# MCU.net
KiCad netlist of a schematic drawn in Altium Designer
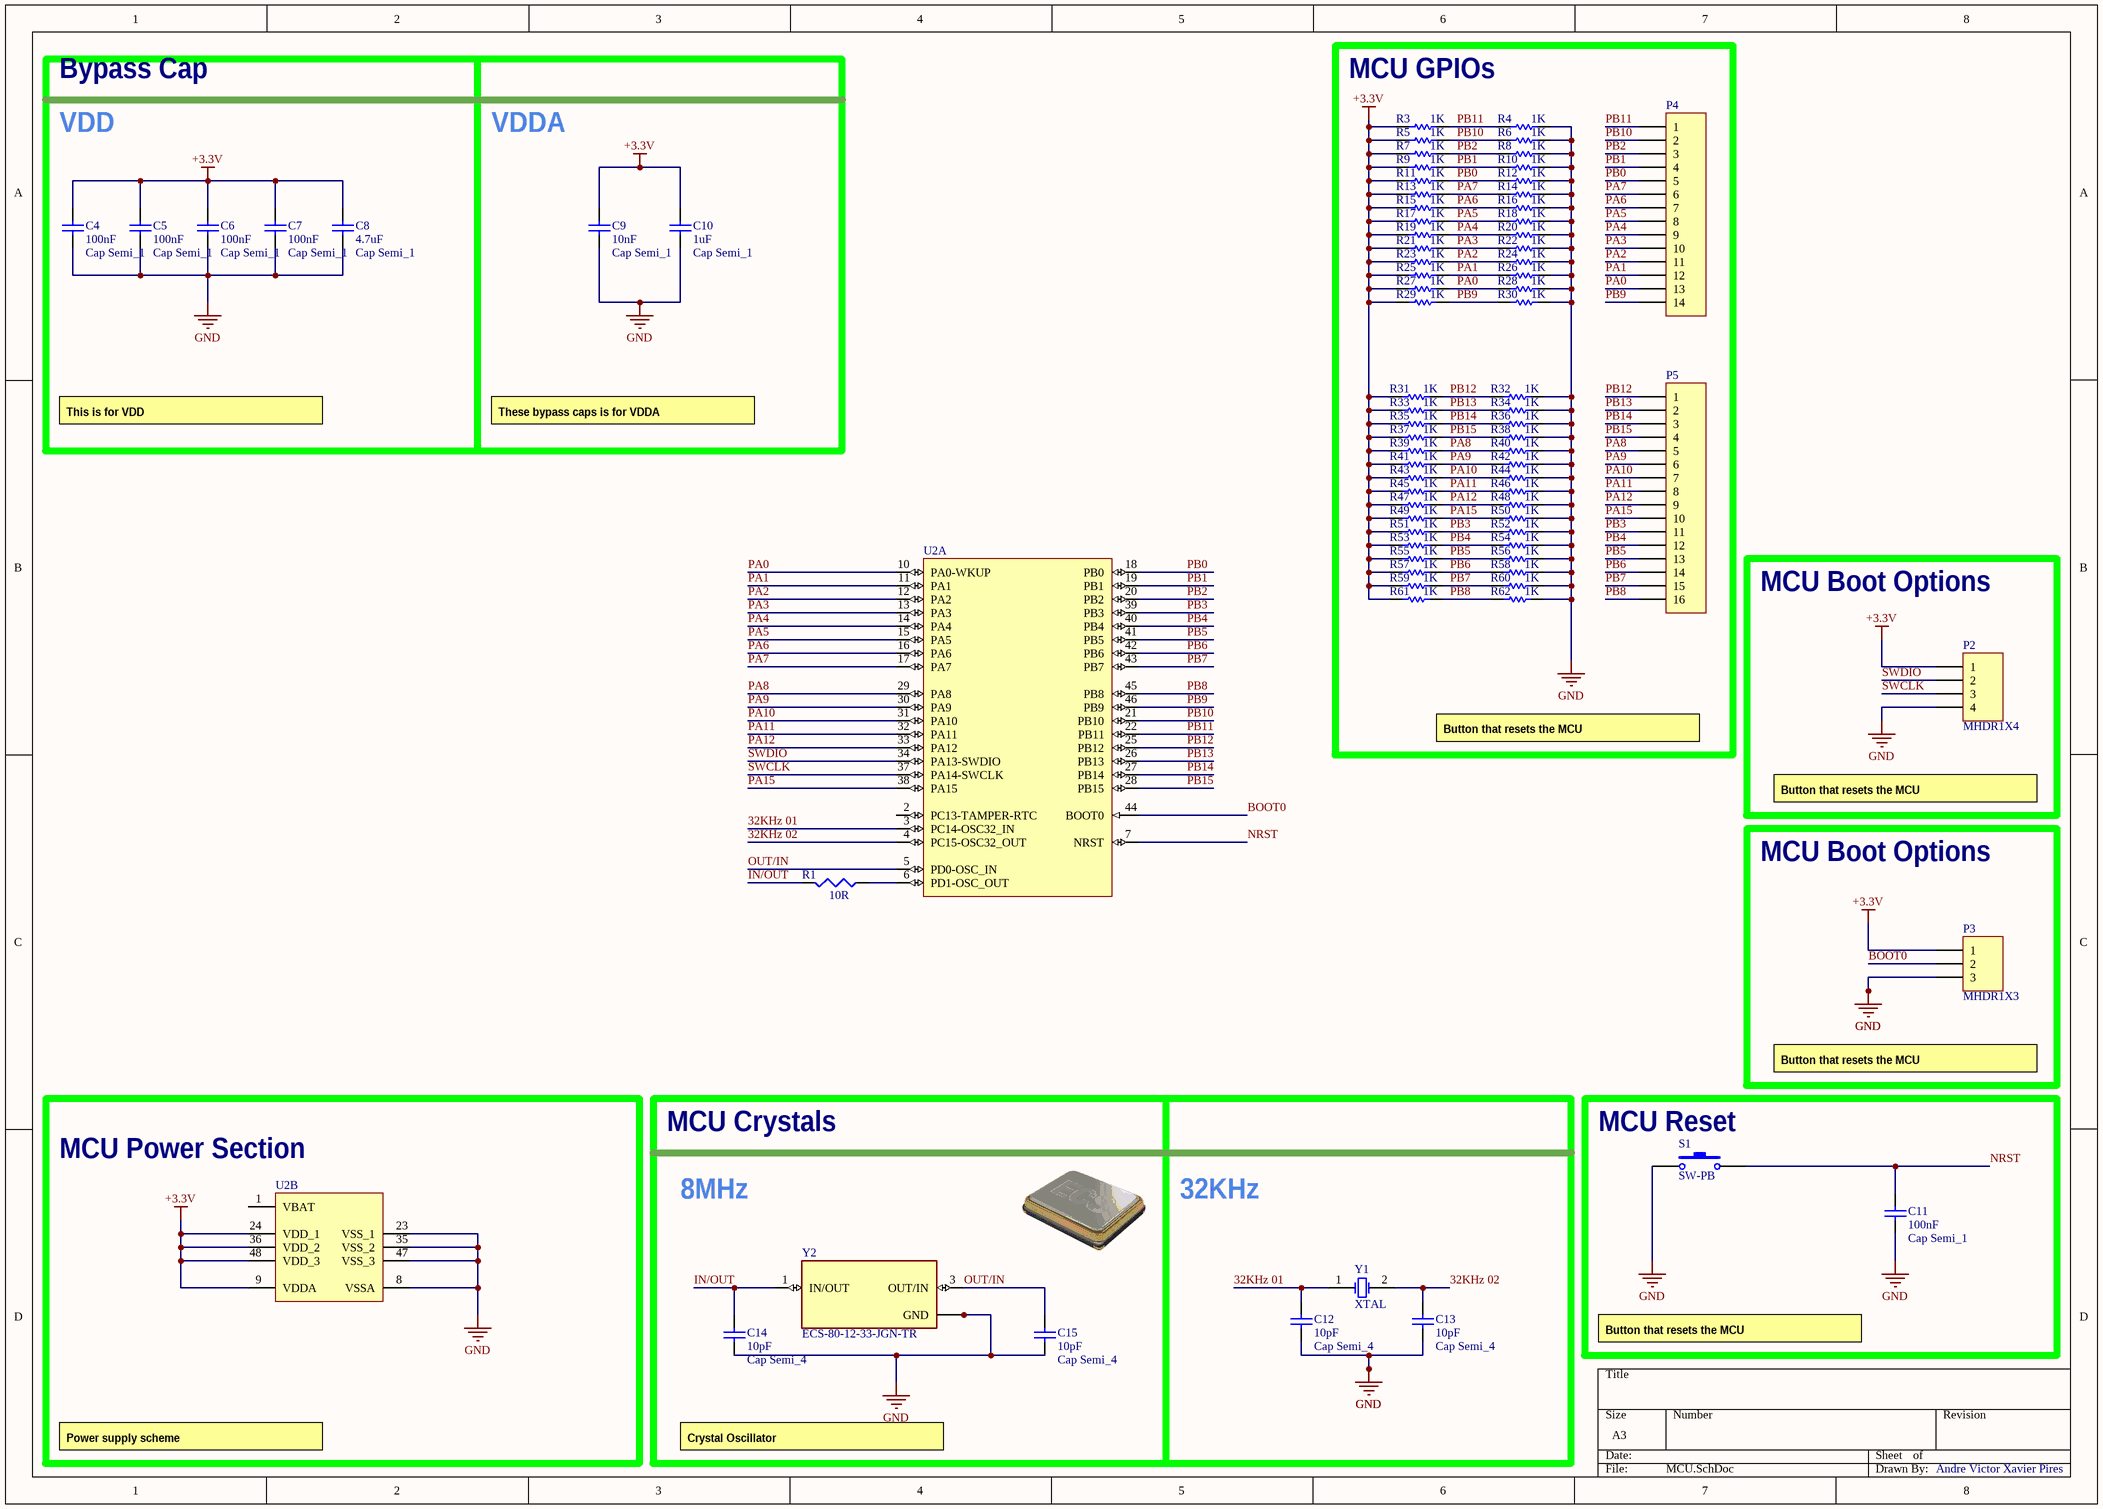
[diagram p0: MCU.SchDoc]

(export (version "E")
  (design (tool "Eeschema 10.0.6"))
  (components
    (comp (ref "C4")
      (value "Cap Semi_1")
      (footprint "1608[0603]cap")
      (description "Capacitor (Semiconductor SIM Model)")
      (fields (field (name "ALTIUM_VALUE") "100nF") (field (name "PUBLISHER") "Altium Limited"))
      (libsource (lib "smartmcu") (part "Cap Semi_1"))
    )
    (comp (ref "C5")
      (value "Cap Semi_1")
      (footprint "1608[0603]cap")
      (description "Capacitor (Semiconductor SIM Model)")
      (fields (field (name "ALTIUM_VALUE") "100nF") (field (name "PUBLISHER") "Altium Limited"))
      (libsource (lib "smartmcu") (part "Cap Semi_1"))
    )
    (comp (ref "C6")
      (value "Cap Semi_1")
      (footprint "1608[0603]cap")
      (description "Capacitor (Semiconductor SIM Model)")
      (fields (field (name "ALTIUM_VALUE") "100nF") (field (name "PUBLISHER") "Altium Limited"))
      (libsource (lib "smartmcu") (part "Cap Semi_1"))
    )
    (comp (ref "C7")
      (value "Cap Semi_1")
      (footprint "1608[0603]cap")
      (description "Capacitor (Semiconductor SIM Model)")
      (fields (field (name "ALTIUM_VALUE") "100nF") (field (name "PUBLISHER") "Altium Limited"))
      (libsource (lib "smartmcu") (part "Cap Semi_1"))
    )
    (comp (ref "C8")
      (value "Cap Semi_1")
      (footprint "1608[0603]cap")
      (description "Capacitor (Semiconductor SIM Model)")
      (fields (field (name "ALTIUM_VALUE") "4.7uF") (field (name "PUBLISHER") "Altium Limited"))
      (libsource (lib "smartmcu") (part "Cap Semi_1_1"))
    )
    (comp (ref "C9")
      (value "Cap Semi_1")
      (footprint "1608[0603]cap")
      (description "Capacitor (Semiconductor SIM Model)")
      (fields (field (name "ALTIUM_VALUE") "10nF") (field (name "PUBLISHER") "Altium Limited"))
      (libsource (lib "smartmcu") (part "Cap Semi_1_2"))
    )
    (comp (ref "C10")
      (value "Cap Semi_1")
      (footprint "1608[0603]cap")
      (description "Capacitor (Semiconductor SIM Model)")
      (fields (field (name "ALTIUM_VALUE") "1uF") (field (name "PUBLISHER") "Altium Limited"))
      (libsource (lib "smartmcu") (part "Cap Semi_1_3"))
    )
    (comp (ref "C11")
      (value "Cap Semi_1")
      (footprint "1608[0603]cap")
      (description "Capacitor (Semiconductor SIM Model)")
      (fields (field (name "ALTIUM_VALUE") "100nF") (field (name "PUBLISHER") "Altium Limited"))
      (libsource (lib "smartmcu") (part "Cap Semi_1"))
    )
    (comp (ref "C12")
      (value "Cap Semi_4")
      (footprint "0402cap")
      (description "Capacitor (Semiconductor SIM Model)")
      (fields (field (name "ALTIUM_VALUE") "10pF") (field (name "PUBLISHER") "Altium Limited"))
      (libsource (lib "smartmcu") (part "Cap Semi_4"))
    )
    (comp (ref "C13")
      (value "Cap Semi_4")
      (footprint "0402cap")
      (description "Capacitor (Semiconductor SIM Model)")
      (fields (field (name "ALTIUM_VALUE") "10pF") (field (name "PUBLISHER") "Altium Limited"))
      (libsource (lib "smartmcu") (part "Cap Semi_4"))
    )
    (comp (ref "C14")
      (value "Cap Semi_4")
      (footprint "0402cap")
      (description "Capacitor (Semiconductor SIM Model)")
      (fields (field (name "ALTIUM_VALUE") "10pF") (field (name "PUBLISHER") "Altium Limited"))
      (libsource (lib "smartmcu") (part "Cap Semi_4"))
    )
    (comp (ref "C15")
      (value "Cap Semi_4")
      (footprint "0402cap")
      (description "Capacitor (Semiconductor SIM Model)")
      (fields (field (name "ALTIUM_VALUE") "10pF") (field (name "PUBLISHER") "Altium Limited"))
      (libsource (lib "smartmcu") (part "Cap Semi_4"))
    )
    (comp (ref "P2")
      (value "MHDR1X4")
      (footprint "MHDR1X4body")
      (description "Header, 4-Pin")
      (fields (field (name "PUBLISHER") "Altium Limited"))
      (libsource (lib "smartmcu") (part "MHDR1X4"))
    )
    (comp (ref "P3")
      (value "MHDR1X3")
      (footprint "MHDR1X3body")
      (description "Header, 3-Pin")
      (fields (field (name "PUBLISHER") "Altium Limited"))
      (libsource (lib "smartmcu") (part "MHDR1X3"))
    )
    (comp (ref "P4")
      (value "~")
      (footprint "MY_FE14")
      (description "Header, 14-Pin")
      (fields (field (name "ASID PART NUMBER") "Header 14-AS"))
      (libsource (lib "smartmcu") (part "Header 14"))
    )
    (comp (ref "P5")
      (value "~")
      (footprint "MY_FE16")
      (description "Header, 16-Pin")
      (fields (field (name "ASID PART NUMBER") "Header 16-AS"))
      (libsource (lib "smartmcu") (part "Header 16"))
    )
    (comp (ref "R1")
      (value "10R")
      (footprint "J1-0603")
      (description "Resistor")
      (fields (field (name "Comment") "Res3") (field (name "PUBLISHER") "Altium Limited"))
      (libsource (lib "Miscellaneous Devices") (part "Res3"))
    )
    (comp (ref "R3")
      (value "1K")
      (footprint "MY_0603")
      (description "Standard resistor")
      (fields (field (name "ASID PART NUMBER") "Res-AS"))
      (libsource (lib "smartmcu") (part "Res"))
    )
    (comp (ref "R4")
      (value "1K")
      (footprint "MY_0603")
      (description "Standard resistor")
      (fields (field (name "ASID PART NUMBER") "Res-AS"))
      (libsource (lib "smartmcu") (part "Res"))
    )
    (comp (ref "R5")
      (value "1K")
      (footprint "MY_0603")
      (description "Standard resistor")
      (fields (field (name "ASID PART NUMBER") "Res-AS"))
      (libsource (lib "smartmcu") (part "Res"))
    )
    (comp (ref "R6")
      (value "1K")
      (footprint "MY_0603")
      (description "Standard resistor")
      (fields (field (name "ASID PART NUMBER") "Res-AS"))
      (libsource (lib "smartmcu") (part "Res"))
    )
    (comp (ref "R7")
      (value "1K")
      (footprint "MY_0603")
      (description "Standard resistor")
      (fields (field (name "ASID PART NUMBER") "Res-AS"))
      (libsource (lib "smartmcu") (part "Res"))
    )
    (comp (ref "R8")
      (value "1K")
      (footprint "MY_0603")
      (description "Standard resistor")
      (fields (field (name "ASID PART NUMBER") "Res-AS"))
      (libsource (lib "smartmcu") (part "Res"))
    )
    (comp (ref "R9")
      (value "1K")
      (footprint "MY_0603")
      (description "Standard resistor")
      (fields (field (name "ASID PART NUMBER") "Res-AS"))
      (libsource (lib "smartmcu") (part "Res"))
    )
    (comp (ref "R10")
      (value "1K")
      (footprint "MY_0603")
      (description "Standard resistor")
      (fields (field (name "ASID PART NUMBER") "Res-AS"))
      (libsource (lib "smartmcu") (part "Res"))
    )
    (comp (ref "R11")
      (value "1K")
      (footprint "MY_0603")
      (description "Standard resistor")
      (fields (field (name "ASID PART NUMBER") "Res-AS"))
      (libsource (lib "smartmcu") (part "Res"))
    )
    (comp (ref "R12")
      (value "1K")
      (footprint "MY_0603")
      (description "Standard resistor")
      (fields (field (name "ASID PART NUMBER") "Res-AS"))
      (libsource (lib "smartmcu") (part "Res"))
    )
    (comp (ref "R13")
      (value "1K")
      (footprint "MY_0603")
      (description "Standard resistor")
      (fields (field (name "ASID PART NUMBER") "Res-AS"))
      (libsource (lib "smartmcu") (part "Res"))
    )
    (comp (ref "R14")
      (value "1K")
      (footprint "MY_0603")
      (description "Standard resistor")
      (fields (field (name "ASID PART NUMBER") "Res-AS"))
      (libsource (lib "smartmcu") (part "Res"))
    )
    (comp (ref "R15")
      (value "1K")
      (footprint "MY_0603")
      (description "Standard resistor")
      (fields (field (name "ASID PART NUMBER") "Res-AS"))
      (libsource (lib "smartmcu") (part "Res"))
    )
    (comp (ref "R16")
      (value "1K")
      (footprint "MY_0603")
      (description "Standard resistor")
      (fields (field (name "ASID PART NUMBER") "Res-AS"))
      (libsource (lib "smartmcu") (part "Res"))
    )
    (comp (ref "R17")
      (value "1K")
      (footprint "MY_0603")
      (description "Standard resistor")
      (fields (field (name "ASID PART NUMBER") "Res-AS"))
      (libsource (lib "smartmcu") (part "Res"))
    )
    (comp (ref "R18")
      (value "1K")
      (footprint "MY_0603")
      (description "Standard resistor")
      (fields (field (name "ASID PART NUMBER") "Res-AS"))
      (libsource (lib "smartmcu") (part "Res"))
    )
    (comp (ref "R19")
      (value "1K")
      (footprint "MY_0603")
      (description "Standard resistor")
      (fields (field (name "ASID PART NUMBER") "Res-AS"))
      (libsource (lib "smartmcu") (part "Res"))
    )
    (comp (ref "R20")
      (value "1K")
      (footprint "MY_0603")
      (description "Standard resistor")
      (fields (field (name "ASID PART NUMBER") "Res-AS"))
      (libsource (lib "smartmcu") (part "Res"))
    )
    (comp (ref "R21")
      (value "1K")
      (footprint "MY_0603")
      (description "Standard resistor")
      (fields (field (name "ASID PART NUMBER") "Res-AS"))
      (libsource (lib "smartmcu") (part "Res"))
    )
    (comp (ref "R22")
      (value "1K")
      (footprint "MY_0603")
      (description "Standard resistor")
      (fields (field (name "ASID PART NUMBER") "Res-AS"))
      (libsource (lib "smartmcu") (part "Res"))
    )
    (comp (ref "R23")
      (value "1K")
      (footprint "MY_0603")
      (description "Standard resistor")
      (fields (field (name "ASID PART NUMBER") "Res-AS"))
      (libsource (lib "smartmcu") (part "Res"))
    )
    (comp (ref "R24")
      (value "1K")
      (footprint "MY_0603")
      (description "Standard resistor")
      (fields (field (name "ASID PART NUMBER") "Res-AS"))
      (libsource (lib "smartmcu") (part "Res"))
    )
    (comp (ref "R25")
      (value "1K")
      (footprint "MY_0603")
      (description "Standard resistor")
      (fields (field (name "ASID PART NUMBER") "Res-AS"))
      (libsource (lib "smartmcu") (part "Res"))
    )
    (comp (ref "R26")
      (value "1K")
      (footprint "MY_0603")
      (description "Standard resistor")
      (fields (field (name "ASID PART NUMBER") "Res-AS"))
      (libsource (lib "smartmcu") (part "Res"))
    )
    (comp (ref "R27")
      (value "1K")
      (footprint "MY_0603")
      (description "Standard resistor")
      (fields (field (name "ASID PART NUMBER") "Res-AS"))
      (libsource (lib "smartmcu") (part "Res"))
    )
    (comp (ref "R28")
      (value "1K")
      (footprint "MY_0603")
      (description "Standard resistor")
      (fields (field (name "ASID PART NUMBER") "Res-AS"))
      (libsource (lib "smartmcu") (part "Res"))
    )
    (comp (ref "R29")
      (value "1K")
      (footprint "MY_0603")
      (description "Standard resistor")
      (fields (field (name "ASID PART NUMBER") "Res-AS"))
      (libsource (lib "smartmcu") (part "Res"))
    )
    (comp (ref "R30")
      (value "1K")
      (footprint "MY_0603")
      (description "Standard resistor")
      (fields (field (name "ASID PART NUMBER") "Res-AS"))
      (libsource (lib "smartmcu") (part "Res"))
    )
    (comp (ref "R31")
      (value "1K")
      (footprint "MY_0603")
      (description "Standard resistor")
      (fields (field (name "ASID PART NUMBER") "Res-AS"))
      (libsource (lib "smartmcu") (part "Res"))
    )
    (comp (ref "R32")
      (value "1K")
      (footprint "MY_0603")
      (description "Standard resistor")
      (fields (field (name "ASID PART NUMBER") "Res-AS"))
      (libsource (lib "smartmcu") (part "Res"))
    )
    (comp (ref "R33")
      (value "1K")
      (footprint "MY_0603")
      (description "Standard resistor")
      (fields (field (name "ASID PART NUMBER") "Res-AS"))
      (libsource (lib "smartmcu") (part "Res"))
    )
    (comp (ref "R34")
      (value "1K")
      (footprint "MY_0603")
      (description "Standard resistor")
      (fields (field (name "ASID PART NUMBER") "Res-AS"))
      (libsource (lib "smartmcu") (part "Res"))
    )
    (comp (ref "R35")
      (value "1K")
      (footprint "MY_0603")
      (description "Standard resistor")
      (fields (field (name "ASID PART NUMBER") "Res-AS"))
      (libsource (lib "smartmcu") (part "Res"))
    )
    (comp (ref "R36")
      (value "1K")
      (footprint "MY_0603")
      (description "Standard resistor")
      (fields (field (name "ASID PART NUMBER") "Res-AS"))
      (libsource (lib "smartmcu") (part "Res"))
    )
    (comp (ref "R37")
      (value "1K")
      (footprint "MY_0603")
      (description "Standard resistor")
      (fields (field (name "ASID PART NUMBER") "Res-AS"))
      (libsource (lib "smartmcu") (part "Res"))
    )
    (comp (ref "R38")
      (value "1K")
      (footprint "MY_0603")
      (description "Standard resistor")
      (fields (field (name "ASID PART NUMBER") "Res-AS"))
      (libsource (lib "smartmcu") (part "Res"))
    )
    (comp (ref "R39")
      (value "1K")
      (footprint "MY_0603")
      (description "Standard resistor")
      (fields (field (name "ASID PART NUMBER") "Res-AS"))
      (libsource (lib "smartmcu") (part "Res"))
    )
    (comp (ref "R40")
      (value "1K")
      (footprint "MY_0603")
      (description "Standard resistor")
      (fields (field (name "ASID PART NUMBER") "Res-AS"))
      (libsource (lib "smartmcu") (part "Res"))
    )
    (comp (ref "R41")
      (value "1K")
      (footprint "MY_0603")
      (description "Standard resistor")
      (fields (field (name "ASID PART NUMBER") "Res-AS"))
      (libsource (lib "smartmcu") (part "Res"))
    )
    (comp (ref "R42")
      (value "1K")
      (footprint "MY_0603")
      (description "Standard resistor")
      (fields (field (name "ASID PART NUMBER") "Res-AS"))
      (libsource (lib "smartmcu") (part "Res"))
    )
    (comp (ref "R43")
      (value "1K")
      (footprint "MY_0603")
      (description "Standard resistor")
      (fields (field (name "ASID PART NUMBER") "Res-AS"))
      (libsource (lib "smartmcu") (part "Res"))
    )
    (comp (ref "R44")
      (value "1K")
      (footprint "MY_0603")
      (description "Standard resistor")
      (fields (field (name "ASID PART NUMBER") "Res-AS"))
      (libsource (lib "smartmcu") (part "Res"))
    )
    (comp (ref "R45")
      (value "1K")
      (footprint "MY_0603")
      (description "Standard resistor")
      (fields (field (name "ASID PART NUMBER") "Res-AS"))
      (libsource (lib "smartmcu") (part "Res"))
    )
    (comp (ref "R46")
      (value "1K")
      (footprint "MY_0603")
      (description "Standard resistor")
      (fields (field (name "ASID PART NUMBER") "Res-AS"))
      (libsource (lib "smartmcu") (part "Res"))
    )
    (comp (ref "R47")
      (value "1K")
      (footprint "MY_0603")
      (description "Standard resistor")
      (fields (field (name "ASID PART NUMBER") "Res-AS"))
      (libsource (lib "smartmcu") (part "Res"))
    )
    (comp (ref "R48")
      (value "1K")
      (footprint "MY_0603")
      (description "Standard resistor")
      (fields (field (name "ASID PART NUMBER") "Res-AS"))
      (libsource (lib "smartmcu") (part "Res"))
    )
    (comp (ref "R49")
      (value "1K")
      (footprint "MY_0603")
      (description "Standard resistor")
      (fields (field (name "ASID PART NUMBER") "Res-AS"))
      (libsource (lib "smartmcu") (part "Res"))
    )
    (comp (ref "R50")
      (value "1K")
      (footprint "MY_0603")
      (description "Standard resistor")
      (fields (field (name "ASID PART NUMBER") "Res-AS"))
      (libsource (lib "smartmcu") (part "Res"))
    )
    (comp (ref "R51")
      (value "1K")
      (footprint "MY_0603")
      (description "Standard resistor")
      (fields (field (name "ASID PART NUMBER") "Res-AS"))
      (libsource (lib "smartmcu") (part "Res"))
    )
    (comp (ref "R52")
      (value "1K")
      (footprint "MY_0603")
      (description "Standard resistor")
      (fields (field (name "ASID PART NUMBER") "Res-AS"))
      (libsource (lib "smartmcu") (part "Res"))
    )
    (comp (ref "R53")
      (value "1K")
      (footprint "MY_0603")
      (description "Standard resistor")
      (fields (field (name "ASID PART NUMBER") "Res-AS"))
      (libsource (lib "smartmcu") (part "Res"))
    )
    (comp (ref "R54")
      (value "1K")
      (footprint "MY_0603")
      (description "Standard resistor")
      (fields (field (name "ASID PART NUMBER") "Res-AS"))
      (libsource (lib "smartmcu") (part "Res"))
    )
    (comp (ref "R55")
      (value "1K")
      (footprint "MY_0603")
      (description "Standard resistor")
      (fields (field (name "ASID PART NUMBER") "Res-AS"))
      (libsource (lib "smartmcu") (part "Res"))
    )
    (comp (ref "R56")
      (value "1K")
      (footprint "MY_0603")
      (description "Standard resistor")
      (fields (field (name "ASID PART NUMBER") "Res-AS"))
      (libsource (lib "smartmcu") (part "Res"))
    )
    (comp (ref "R57")
      (value "1K")
      (footprint "MY_0603")
      (description "Standard resistor")
      (fields (field (name "ASID PART NUMBER") "Res-AS"))
      (libsource (lib "smartmcu") (part "Res"))
    )
    (comp (ref "R58")
      (value "1K")
      (footprint "MY_0603")
      (description "Standard resistor")
      (fields (field (name "ASID PART NUMBER") "Res-AS"))
      (libsource (lib "smartmcu") (part "Res"))
    )
    (comp (ref "R59")
      (value "1K")
      (footprint "MY_0603")
      (description "Standard resistor")
      (fields (field (name "ASID PART NUMBER") "Res-AS"))
      (libsource (lib "smartmcu") (part "Res"))
    )
    (comp (ref "R60")
      (value "1K")
      (footprint "MY_0603")
      (description "Standard resistor")
      (fields (field (name "ASID PART NUMBER") "Res-AS"))
      (libsource (lib "smartmcu") (part "Res"))
    )
    (comp (ref "R61")
      (value "1K")
      (footprint "MY_0603")
      (description "Standard resistor")
      (fields (field (name "ASID PART NUMBER") "Res-AS"))
      (libsource (lib "smartmcu") (part "Res"))
    )
    (comp (ref "R62")
      (value "1K")
      (footprint "MY_0603")
      (description "Standard resistor")
      (fields (field (name "ASID PART NUMBER") "Res-AS"))
      (libsource (lib "smartmcu") (part "Res"))
    )
    (comp (ref "S1")
      (value "SW-PB")
      (footprint "SPST-2_body")
      (description "Switch")
      (fields (field (name "PUBLISHER") "Altium Limited"))
      (libsource (lib "smartmcu") (part "SW-PB"))
    )
    (comp (ref "U2")
      (value "~")
      (footprint "STM-LQFP48_N")
      (fields (field (name "PARTNUMBER") "STM32F103C8T6"))
      (libsource (lib "smartmcu") (part "STM32F103C8T6"))
    )
    (comp (ref "Y1")
      (value "XTAL")
      (footprint "32768")
      (description "Crystal Oscillator")
      (fields (field (name "PUBLISHER") "Altium Limited"))
      (libsource (lib "smartmcu") (part "XTAL"))
    )
    (comp (ref "Y2")
      (value "ECS-80-12-33-JGN-TR")
      (footprint "8MHZCrystall")
      (description "8MHz Â±20ppm Crystal 12pF 400 Ohms 4-SMD, No Lead")
      (fields
        (field (name "MF") "ECS Inc.")
        (field (name "BUYPART") "https://www.snapeda.com/parts/ECS-80-12-33-JGN-TR/ECS%20Inc./view-part/4477300/?ref=eda")
      )
      (libsource (lib "smartmcu") (part "ECS-80-12-33-JGN-TR"))
    )
  )
  (nets
    (net (code "1") (name "+3.3V") (class "Default")
      (node (ref "C10") (pin "1") (pinfunction "1_1") (pintype "passive"))
      (node (ref "C4") (pin "1") (pinfunction "1_1") (pintype "passive"))
      (node (ref "C5") (pin "1") (pinfunction "1_1") (pintype "passive"))
      (node (ref "C6") (pin "1") (pinfunction "1_1") (pintype "passive"))
      (node (ref "C7") (pin "1") (pinfunction "1_1") (pintype "passive"))
      (node (ref "C8") (pin "1") (pinfunction "1_1") (pintype "passive"))
      (node (ref "C9") (pin "1") (pinfunction "1_1") (pintype "passive"))
      (node (ref "P2") (pin "1") (pinfunction "1_1") (pintype "passive"))
      (node (ref "P3") (pin "1") (pinfunction "1_1") (pintype "passive"))
      (node (ref "R11") (pin "2") (pinfunction "2_2") (pintype "passive"))
      (node (ref "R13") (pin "2") (pinfunction "2_2") (pintype "passive"))
      (node (ref "R15") (pin "2") (pinfunction "2_2") (pintype "passive"))
      (node (ref "R17") (pin "2") (pinfunction "2_2") (pintype "passive"))
      (node (ref "R19") (pin "2") (pinfunction "2_2") (pintype "passive"))
      (node (ref "R21") (pin "2") (pinfunction "2_2") (pintype "passive"))
      (node (ref "R23") (pin "2") (pinfunction "2_2") (pintype "passive"))
      (node (ref "R25") (pin "2") (pinfunction "2_2") (pintype "passive"))
      (node (ref "R27") (pin "2") (pinfunction "2_2") (pintype "passive"))
      (node (ref "R29") (pin "2") (pinfunction "2_2") (pintype "passive"))
      (node (ref "R3") (pin "2") (pinfunction "2_2") (pintype "passive"))
      (node (ref "R31") (pin "2") (pinfunction "2_2") (pintype "passive"))
      (node (ref "R33") (pin "2") (pinfunction "2_2") (pintype "passive"))
      (node (ref "R35") (pin "2") (pinfunction "2_2") (pintype "passive"))
      (node (ref "R37") (pin "2") (pinfunction "2_2") (pintype "passive"))
      (node (ref "R39") (pin "2") (pinfunction "2_2") (pintype "passive"))
      (node (ref "R41") (pin "2") (pinfunction "2_2") (pintype "passive"))
      (node (ref "R43") (pin "2") (pinfunction "2_2") (pintype "passive"))
      (node (ref "R45") (pin "2") (pinfunction "2_2") (pintype "passive"))
      (node (ref "R47") (pin "2") (pinfunction "2_2") (pintype "passive"))
      (node (ref "R49") (pin "2") (pinfunction "2_2") (pintype "passive"))
      (node (ref "R5") (pin "2") (pinfunction "2_2") (pintype "passive"))
      (node (ref "R51") (pin "2") (pinfunction "2_2") (pintype "passive"))
      (node (ref "R53") (pin "2") (pinfunction "2_2") (pintype "passive"))
      (node (ref "R55") (pin "2") (pinfunction "2_2") (pintype "passive"))
      (node (ref "R57") (pin "2") (pinfunction "2_2") (pintype "passive"))
      (node (ref "R59") (pin "2") (pinfunction "2_2") (pintype "passive"))
      (node (ref "R61") (pin "2") (pinfunction "2_2") (pintype "passive"))
      (node (ref "R7") (pin "2") (pinfunction "2_2") (pintype "passive"))
      (node (ref "R9") (pin "2") (pinfunction "2_2") (pintype "passive"))
      (node (ref "U2") (pin "24") (pinfunction "VDD_1_24") (pintype "power_in"))
      (node (ref "U2") (pin "36") (pinfunction "VDD_2_36") (pintype "power_in"))
      (node (ref "U2") (pin "48") (pinfunction "VDD_3_48") (pintype "power_in"))
      (node (ref "U2") (pin "9") (pinfunction "VDDA_9") (pintype "power_in"))
    )
    (net (code "2") (name "/32KHz 01") (class "Default")
      (node (ref "C12") (pin "2") (pinfunction "2_2") (pintype "passive"))
      (node (ref "U2") (pin "3") (pinfunction "PC14-OSC32_IN_3") (pintype "bidirectional"))
      (node (ref "Y1") (pin "1") (pinfunction "OSC1_1") (pintype "passive"))
    )
    (net (code "3") (name "/32KHz 02") (class "Default")
      (node (ref "C13") (pin "2") (pinfunction "2_2") (pintype "passive"))
      (node (ref "U2") (pin "4") (pinfunction "PC15-OSC32_OUT_4") (pintype "bidirectional"))
      (node (ref "Y1") (pin "2") (pinfunction "OSC2_2") (pintype "passive"))
    )
    (net (code "4") (name "/BOOT0") (class "Default")
      (node (ref "P3") (pin "2") (pinfunction "2_2") (pintype "passive"))
      (node (ref "U2") (pin "44") (pinfunction "BOOT0_44") (pintype "input"))
    )
    (net (code "5") (name "/IN{slash}OUT") (class "Default")
      (node (ref "C14") (pin "2") (pinfunction "2_2") (pintype "passive"))
      (node (ref "R1") (pin "2") (pinfunction "2_2") (pintype "passive"))
      (node (ref "Y2") (pin "1") (pinfunction "IN/OUT_1") (pintype "bidirectional"))
    )
    (net (code "6") (name "/NRST") (class "Default")
      (node (ref "C11") (pin "1") (pinfunction "1_1") (pintype "passive"))
      (node (ref "S1") (pin "2") (pinfunction "2_2") (pintype "passive"))
      (node (ref "U2") (pin "7") (pinfunction "NRST_7") (pintype "bidirectional"))
    )
    (net (code "7") (name "/OUT{slash}IN") (class "Default")
      (node (ref "C15") (pin "2") (pinfunction "2_2") (pintype "passive"))
      (node (ref "U2") (pin "5") (pinfunction "PD0-OSC_IN_5") (pintype "bidirectional"))
      (node (ref "Y2") (pin "3") (pinfunction "OUT/IN_3") (pintype "bidirectional"))
    )
    (net (code "8") (name "/PA0") (class "Default")
      (node (ref "P4") (pin "13") (pinfunction "13_13") (pintype "passive"))
      (node (ref "R27") (pin "1") (pinfunction "1_1") (pintype "passive"))
      (node (ref "R28") (pin "2") (pinfunction "2_2") (pintype "passive"))
      (node (ref "U2") (pin "10") (pinfunction "PA0-WKUP_10") (pintype "bidirectional"))
    )
    (net (code "9") (name "/PA1") (class "Default")
      (node (ref "P4") (pin "12") (pinfunction "12_12") (pintype "passive"))
      (node (ref "R25") (pin "1") (pinfunction "1_1") (pintype "passive"))
      (node (ref "R26") (pin "2") (pinfunction "2_2") (pintype "passive"))
      (node (ref "U2") (pin "11") (pinfunction "PA1_11") (pintype "bidirectional"))
    )
    (net (code "10") (name "/PA2") (class "Default")
      (node (ref "P4") (pin "11") (pinfunction "11_11") (pintype "passive"))
      (node (ref "R23") (pin "1") (pinfunction "1_1") (pintype "passive"))
      (node (ref "R24") (pin "2") (pinfunction "2_2") (pintype "passive"))
      (node (ref "U2") (pin "12") (pinfunction "PA2_12") (pintype "bidirectional"))
    )
    (net (code "11") (name "/PA3") (class "Default")
      (node (ref "P4") (pin "10") (pinfunction "10_10") (pintype "passive"))
      (node (ref "R21") (pin "1") (pinfunction "1_1") (pintype "passive"))
      (node (ref "R22") (pin "2") (pinfunction "2_2") (pintype "passive"))
      (node (ref "U2") (pin "13") (pinfunction "PA3_13") (pintype "bidirectional"))
    )
    (net (code "12") (name "/PA4") (class "Default")
      (node (ref "P4") (pin "9") (pinfunction "9_9") (pintype "passive"))
      (node (ref "R19") (pin "1") (pinfunction "1_1") (pintype "passive"))
      (node (ref "R20") (pin "2") (pinfunction "2_2") (pintype "passive"))
      (node (ref "U2") (pin "14") (pinfunction "PA4_14") (pintype "bidirectional"))
    )
    (net (code "13") (name "/PA5") (class "Default")
      (node (ref "P4") (pin "8") (pinfunction "8_8") (pintype "passive"))
      (node (ref "R17") (pin "1") (pinfunction "1_1") (pintype "passive"))
      (node (ref "R18") (pin "2") (pinfunction "2_2") (pintype "passive"))
      (node (ref "U2") (pin "15") (pinfunction "PA5_15") (pintype "bidirectional"))
    )
    (net (code "14") (name "/PA6") (class "Default")
      (node (ref "P4") (pin "7") (pinfunction "7_7") (pintype "passive"))
      (node (ref "R15") (pin "1") (pinfunction "1_1") (pintype "passive"))
      (node (ref "R16") (pin "2") (pinfunction "2_2") (pintype "passive"))
      (node (ref "U2") (pin "16") (pinfunction "PA6_16") (pintype "bidirectional"))
    )
    (net (code "15") (name "/PA7") (class "Default")
      (node (ref "P4") (pin "6") (pinfunction "6_6") (pintype "passive"))
      (node (ref "R13") (pin "1") (pinfunction "1_1") (pintype "passive"))
      (node (ref "R14") (pin "2") (pinfunction "2_2") (pintype "passive"))
      (node (ref "U2") (pin "17") (pinfunction "PA7_17") (pintype "bidirectional"))
    )
    (net (code "16") (name "/PA8") (class "Default")
      (node (ref "P5") (pin "5") (pinfunction "5_5") (pintype "passive"))
      (node (ref "R39") (pin "1") (pinfunction "1_1") (pintype "passive"))
      (node (ref "R40") (pin "2") (pinfunction "2_2") (pintype "passive"))
      (node (ref "U2") (pin "29") (pinfunction "PA8_29") (pintype "bidirectional"))
    )
    (net (code "17") (name "/PA9") (class "Default")
      (node (ref "P5") (pin "6") (pinfunction "6_6") (pintype "passive"))
      (node (ref "R41") (pin "1") (pinfunction "1_1") (pintype "passive"))
      (node (ref "R42") (pin "2") (pinfunction "2_2") (pintype "passive"))
      (node (ref "U2") (pin "30") (pinfunction "PA9_30") (pintype "bidirectional"))
    )
    (net (code "18") (name "/PA10") (class "Default")
      (node (ref "P5") (pin "7") (pinfunction "7_7") (pintype "passive"))
      (node (ref "R43") (pin "1") (pinfunction "1_1") (pintype "passive"))
      (node (ref "R44") (pin "2") (pinfunction "2_2") (pintype "passive"))
      (node (ref "U2") (pin "31") (pinfunction "PA10_31") (pintype "bidirectional"))
    )
    (net (code "19") (name "/PA11") (class "Default")
      (node (ref "P5") (pin "8") (pinfunction "8_8") (pintype "passive"))
      (node (ref "R45") (pin "1") (pinfunction "1_1") (pintype "passive"))
      (node (ref "R46") (pin "2") (pinfunction "2_2") (pintype "passive"))
      (node (ref "U2") (pin "32") (pinfunction "PA11_32") (pintype "bidirectional"))
    )
    (net (code "20") (name "/PA12") (class "Default")
      (node (ref "P5") (pin "9") (pinfunction "9_9") (pintype "passive"))
      (node (ref "R47") (pin "1") (pinfunction "1_1") (pintype "passive"))
      (node (ref "R48") (pin "2") (pinfunction "2_2") (pintype "passive"))
      (node (ref "U2") (pin "33") (pinfunction "PA12_33") (pintype "bidirectional"))
    )
    (net (code "21") (name "/PA15") (class "Default")
      (node (ref "P5") (pin "10") (pinfunction "10_10") (pintype "passive"))
      (node (ref "R49") (pin "1") (pinfunction "1_1") (pintype "passive"))
      (node (ref "R50") (pin "2") (pinfunction "2_2") (pintype "passive"))
      (node (ref "U2") (pin "38") (pinfunction "PA15_38") (pintype "bidirectional"))
    )
    (net (code "22") (name "/PB0") (class "Default")
      (node (ref "P4") (pin "5") (pinfunction "5_5") (pintype "passive"))
      (node (ref "R11") (pin "1") (pinfunction "1_1") (pintype "passive"))
      (node (ref "R12") (pin "2") (pinfunction "2_2") (pintype "passive"))
      (node (ref "U2") (pin "18") (pinfunction "PB0_18") (pintype "bidirectional"))
    )
    (net (code "23") (name "/PB1") (class "Default")
      (node (ref "P4") (pin "4") (pinfunction "4_4") (pintype "passive"))
      (node (ref "R10") (pin "2") (pinfunction "2_2") (pintype "passive"))
      (node (ref "R9") (pin "1") (pinfunction "1_1") (pintype "passive"))
      (node (ref "U2") (pin "19") (pinfunction "PB1_19") (pintype "bidirectional"))
    )
    (net (code "24") (name "/PB2") (class "Default")
      (node (ref "P4") (pin "3") (pinfunction "3_3") (pintype "passive"))
      (node (ref "R7") (pin "1") (pinfunction "1_1") (pintype "passive"))
      (node (ref "R8") (pin "2") (pinfunction "2_2") (pintype "passive"))
      (node (ref "U2") (pin "20") (pinfunction "PB2_20") (pintype "bidirectional"))
    )
    (net (code "25") (name "/PB3") (class "Default")
      (node (ref "P5") (pin "11") (pinfunction "11_11") (pintype "passive"))
      (node (ref "R51") (pin "1") (pinfunction "1_1") (pintype "passive"))
      (node (ref "R52") (pin "2") (pinfunction "2_2") (pintype "passive"))
      (node (ref "U2") (pin "39") (pinfunction "PB3_39") (pintype "bidirectional"))
    )
    (net (code "26") (name "/PB4") (class "Default")
      (node (ref "P5") (pin "12") (pinfunction "12_12") (pintype "passive"))
      (node (ref "R53") (pin "1") (pinfunction "1_1") (pintype "passive"))
      (node (ref "R54") (pin "2") (pinfunction "2_2") (pintype "passive"))
      (node (ref "U2") (pin "40") (pinfunction "PB4_40") (pintype "bidirectional"))
    )
    (net (code "27") (name "/PB5") (class "Default")
      (node (ref "P5") (pin "13") (pinfunction "13_13") (pintype "passive"))
      (node (ref "R55") (pin "1") (pinfunction "1_1") (pintype "passive"))
      (node (ref "R56") (pin "2") (pinfunction "2_2") (pintype "passive"))
      (node (ref "U2") (pin "41") (pinfunction "PB5_41") (pintype "bidirectional"))
    )
    (net (code "28") (name "/PB6") (class "Default")
      (node (ref "P5") (pin "14") (pinfunction "14_14") (pintype "passive"))
      (node (ref "R57") (pin "1") (pinfunction "1_1") (pintype "passive"))
      (node (ref "R58") (pin "2") (pinfunction "2_2") (pintype "passive"))
      (node (ref "U2") (pin "42") (pinfunction "PB6_42") (pintype "bidirectional"))
    )
    (net (code "29") (name "/PB7") (class "Default")
      (node (ref "P5") (pin "15") (pinfunction "15_15") (pintype "passive"))
      (node (ref "R59") (pin "1") (pinfunction "1_1") (pintype "passive"))
      (node (ref "R60") (pin "2") (pinfunction "2_2") (pintype "passive"))
      (node (ref "U2") (pin "43") (pinfunction "PB7_43") (pintype "bidirectional"))
    )
    (net (code "30") (name "/PB8") (class "Default")
      (node (ref "P5") (pin "16") (pinfunction "16_16") (pintype "passive"))
      (node (ref "R61") (pin "1") (pinfunction "1_1") (pintype "passive"))
      (node (ref "R62") (pin "2") (pinfunction "2_2") (pintype "passive"))
      (node (ref "U2") (pin "45") (pinfunction "PB8_45") (pintype "bidirectional"))
    )
    (net (code "31") (name "/PB9") (class "Default")
      (node (ref "P4") (pin "14") (pinfunction "14_14") (pintype "passive"))
      (node (ref "R29") (pin "1") (pinfunction "1_1") (pintype "passive"))
      (node (ref "R30") (pin "2") (pinfunction "2_2") (pintype "passive"))
      (node (ref "U2") (pin "46") (pinfunction "PB9_46") (pintype "bidirectional"))
    )
    (net (code "32") (name "/PB10") (class "Default")
      (node (ref "P4") (pin "2") (pinfunction "2_2") (pintype "passive"))
      (node (ref "R5") (pin "1") (pinfunction "1_1") (pintype "passive"))
      (node (ref "R6") (pin "2") (pinfunction "2_2") (pintype "passive"))
      (node (ref "U2") (pin "21") (pinfunction "PB10_21") (pintype "bidirectional"))
    )
    (net (code "33") (name "/PB11") (class "Default")
      (node (ref "P4") (pin "1") (pinfunction "1_1") (pintype "passive"))
      (node (ref "R3") (pin "1") (pinfunction "1_1") (pintype "passive"))
      (node (ref "R4") (pin "2") (pinfunction "2_2") (pintype "passive"))
      (node (ref "U2") (pin "22") (pinfunction "PB11_22") (pintype "bidirectional"))
    )
    (net (code "34") (name "/PB12") (class "Default")
      (node (ref "P5") (pin "1") (pinfunction "1_1") (pintype "passive"))
      (node (ref "R31") (pin "1") (pinfunction "1_1") (pintype "passive"))
      (node (ref "R32") (pin "2") (pinfunction "2_2") (pintype "passive"))
      (node (ref "U2") (pin "25") (pinfunction "PB12_25") (pintype "bidirectional"))
    )
    (net (code "35") (name "/PB13") (class "Default")
      (node (ref "P5") (pin "2") (pinfunction "2_2") (pintype "passive"))
      (node (ref "R33") (pin "1") (pinfunction "1_1") (pintype "passive"))
      (node (ref "R34") (pin "2") (pinfunction "2_2") (pintype "passive"))
      (node (ref "U2") (pin "26") (pinfunction "PB13_26") (pintype "bidirectional"))
    )
    (net (code "36") (name "/PB14") (class "Default")
      (node (ref "P5") (pin "3") (pinfunction "3_3") (pintype "passive"))
      (node (ref "R35") (pin "1") (pinfunction "1_1") (pintype "passive"))
      (node (ref "R36") (pin "2") (pinfunction "2_2") (pintype "passive"))
      (node (ref "U2") (pin "27") (pinfunction "PB14_27") (pintype "bidirectional"))
    )
    (net (code "37") (name "/PB15") (class "Default")
      (node (ref "P5") (pin "4") (pinfunction "4_4") (pintype "passive"))
      (node (ref "R37") (pin "1") (pinfunction "1_1") (pintype "passive"))
      (node (ref "R38") (pin "2") (pinfunction "2_2") (pintype "passive"))
      (node (ref "U2") (pin "28") (pinfunction "PB15_28") (pintype "bidirectional"))
    )
    (net (code "38") (name "/SWCLK") (class "Default")
      (node (ref "P2") (pin "3") (pinfunction "3_3") (pintype "passive"))
      (node (ref "U2") (pin "37") (pinfunction "PA14-SWCLK_37") (pintype "bidirectional"))
    )
    (net (code "39") (name "/SWDIO") (class "Default")
      (node (ref "P2") (pin "2") (pinfunction "2_2") (pintype "passive"))
      (node (ref "U2") (pin "34") (pinfunction "PA13-SWDIO_34") (pintype "bidirectional"))
    )
    (net (code "40") (name "GND") (class "Default")
      (node (ref "C10") (pin "2") (pinfunction "2_2") (pintype "passive"))
      (node (ref "C11") (pin "2") (pinfunction "2_2") (pintype "passive"))
      (node (ref "C12") (pin "1") (pinfunction "1_1") (pintype "passive"))
      (node (ref "C13") (pin "1") (pinfunction "1_1") (pintype "passive"))
      (node (ref "C14") (pin "1") (pinfunction "1_1") (pintype "passive"))
      (node (ref "C15") (pin "1") (pinfunction "1_1") (pintype "passive"))
      (node (ref "C4") (pin "2") (pinfunction "2_2") (pintype "passive"))
      (node (ref "C5") (pin "2") (pinfunction "2_2") (pintype "passive"))
      (node (ref "C6") (pin "2") (pinfunction "2_2") (pintype "passive"))
      (node (ref "C7") (pin "2") (pinfunction "2_2") (pintype "passive"))
      (node (ref "C8") (pin "2") (pinfunction "2_2") (pintype "passive"))
      (node (ref "C9") (pin "2") (pinfunction "2_2") (pintype "passive"))
      (node (ref "P2") (pin "4") (pinfunction "4_4") (pintype "passive"))
      (node (ref "P3") (pin "3") (pinfunction "3_3") (pintype "passive"))
      (node (ref "R10") (pin "1") (pinfunction "1_1") (pintype "passive"))
      (node (ref "R12") (pin "1") (pinfunction "1_1") (pintype "passive"))
      (node (ref "R14") (pin "1") (pinfunction "1_1") (pintype "passive"))
      (node (ref "R16") (pin "1") (pinfunction "1_1") (pintype "passive"))
      (node (ref "R18") (pin "1") (pinfunction "1_1") (pintype "passive"))
      (node (ref "R20") (pin "1") (pinfunction "1_1") (pintype "passive"))
      (node (ref "R22") (pin "1") (pinfunction "1_1") (pintype "passive"))
      (node (ref "R24") (pin "1") (pinfunction "1_1") (pintype "passive"))
      (node (ref "R26") (pin "1") (pinfunction "1_1") (pintype "passive"))
      (node (ref "R28") (pin "1") (pinfunction "1_1") (pintype "passive"))
      (node (ref "R30") (pin "1") (pinfunction "1_1") (pintype "passive"))
      (node (ref "R32") (pin "1") (pinfunction "1_1") (pintype "passive"))
      (node (ref "R34") (pin "1") (pinfunction "1_1") (pintype "passive"))
      (node (ref "R36") (pin "1") (pinfunction "1_1") (pintype "passive"))
      (node (ref "R38") (pin "1") (pinfunction "1_1") (pintype "passive"))
      (node (ref "R4") (pin "1") (pinfunction "1_1") (pintype "passive"))
      (node (ref "R40") (pin "1") (pinfunction "1_1") (pintype "passive"))
      (node (ref "R42") (pin "1") (pinfunction "1_1") (pintype "passive"))
      (node (ref "R44") (pin "1") (pinfunction "1_1") (pintype "passive"))
      (node (ref "R46") (pin "1") (pinfunction "1_1") (pintype "passive"))
      (node (ref "R48") (pin "1") (pinfunction "1_1") (pintype "passive"))
      (node (ref "R50") (pin "1") (pinfunction "1_1") (pintype "passive"))
      (node (ref "R52") (pin "1") (pinfunction "1_1") (pintype "passive"))
      (node (ref "R54") (pin "1") (pinfunction "1_1") (pintype "passive"))
      (node (ref "R56") (pin "1") (pinfunction "1_1") (pintype "passive"))
      (node (ref "R58") (pin "1") (pinfunction "1_1") (pintype "passive"))
      (node (ref "R6") (pin "1") (pinfunction "1_1") (pintype "passive"))
      (node (ref "R60") (pin "1") (pinfunction "1_1") (pintype "passive"))
      (node (ref "R62") (pin "1") (pinfunction "1_1") (pintype "passive"))
      (node (ref "R8") (pin "1") (pinfunction "1_1") (pintype "passive"))
      (node (ref "S1") (pin "1") (pinfunction "1_1") (pintype "passive"))
      (node (ref "U2") (pin "23") (pinfunction "VSS_1_23") (pintype "power_in"))
      (node (ref "U2") (pin "35") (pinfunction "VSS_2_35") (pintype "power_in"))
      (node (ref "U2") (pin "47") (pinfunction "VSS_3_47") (pintype "power_in"))
      (node (ref "U2") (pin "8") (pinfunction "VSSA_8") (pintype "power_in"))
      (node (ref "Y2") (pin "2") (pinfunction "GND_2") (pintype "power_in"))
      (node (ref "Y2") (pin "4") (pinfunction "GND_4") (pintype "power_in"))
    )
    (net (code "41") (name "Net-(U2A-PD1-OSC_OUT)") (class "Default")
      (node (ref "R1") (pin "1") (pinfunction "1_1") (pintype "passive"))
      (node (ref "U2") (pin "6") (pinfunction "PD1-OSC_OUT_6") (pintype "bidirectional"))
    )
    (net (code "42") (name "unconnected-(U2A-PC13-TAMPER-RTC-Pad2)") (class "Default")
      (node (ref "U2") (pin "2") (pinfunction "PC13-TAMPER-RTC_2") (pintype "bidirectional"))
    )
    (net (code "43") (name "unconnected-(U2B-VBAT-Pad1)") (class "Default")
      (node (ref "U2") (pin "1") (pinfunction "VBAT_1") (pintype "power_in"))
    )
  )
)
